# crankSignal.net
KiCad netlist of a schematic drawn in Altium Designer
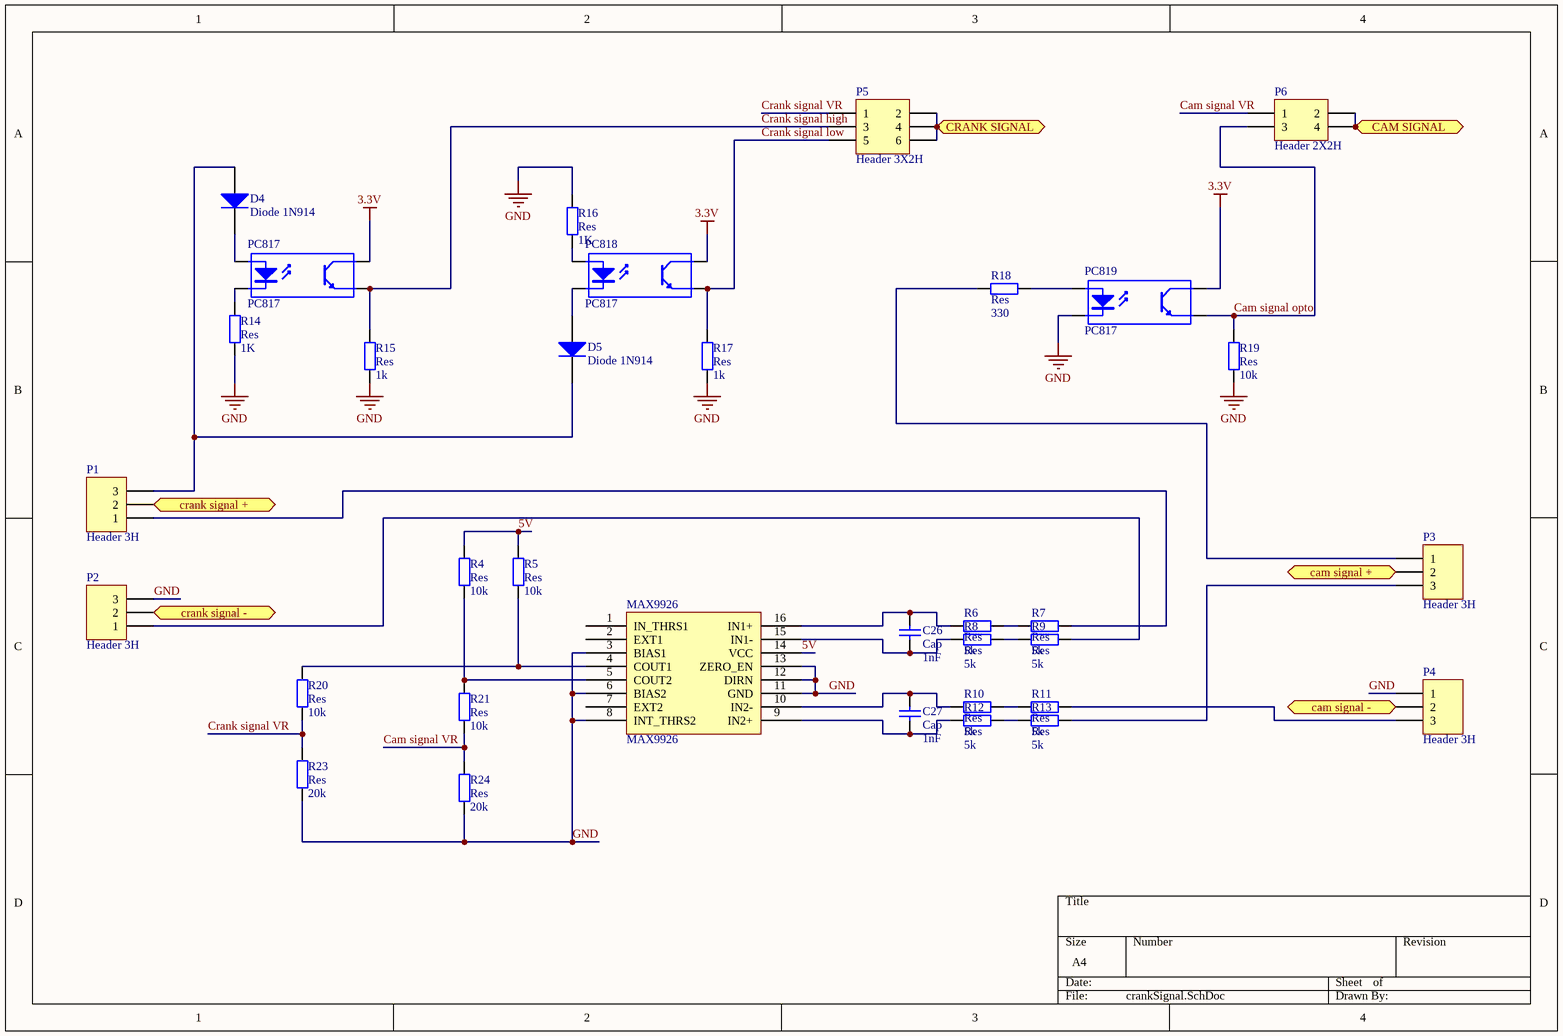
[diagram p0: crankSignal.SchDoc]

(export (version "E")
  (design (tool "Eeschema 10.0.6"))
  (components
    (comp (ref "C26")
      (value "Cap")
      (footprint "1206 footprint")
      (fields (field (name "ALTIUM_VALUE") "1nF"))
      (libsource (lib "ArduinoNano") (part "Cap"))
    )
    (comp (ref "C27")
      (value "Cap")
      (footprint "1206 footprint")
      (fields (field (name "ALTIUM_VALUE") "1nF"))
      (libsource (lib "ArduinoNano") (part "Cap"))
    )
    (comp (ref "D4")
      (value "Diode 1N914")
      (footprint "DO-35")
      (description "High Conductance Fast Diode")
      (fields (field (name "PUBLISHER") "Altium Limited"))
      (libsource (lib "Miscellaneous Devices") (part "Diode 1N914"))
    )
    (comp (ref "D5")
      (value "Diode 1N914")
      (footprint "DO-35")
      (description "High Conductance Fast Diode")
      (fields (field (name "PUBLISHER") "Altium Limited"))
      (libsource (lib "Miscellaneous Devices") (part "Diode 1N914"))
    )
    (comp (ref "MAX9926")
      (value "MAX9926")
      (footprint "MAX9927")
      (libsource (lib "ArduinoNano") (part "MAX9926"))
    )
    (comp (ref "P1")
      (value "Header 3H")
      (footprint "HDR1X3H")
      (description "Header, 3-Pin, Right Angle")
      (fields (field (name "PUBLISHER") "Altium Limited"))
      (libsource (lib "") (part "Header 3H_1"))
    )
    (comp (ref "P2")
      (value "Header 3H")
      (footprint "HDR1X3H")
      (description "Header, 3-Pin, Right Angle")
      (fields (field (name "PUBLISHER") "Altium Limited"))
      (libsource (lib "") (part "Header 3H_1"))
    )
    (comp (ref "P3")
      (value "Header 3H")
      (footprint "HDR1X3H")
      (description "Header, 3-Pin, Right Angle")
      (fields (field (name "PUBLISHER") "Altium Limited"))
      (libsource (lib "Miscellaneous Connectors") (part "Header 3H"))
    )
    (comp (ref "P4")
      (value "Header 3H")
      (footprint "HDR1X3H")
      (description "Header, 3-Pin, Right Angle")
      (fields (field (name "PUBLISHER") "Altium Limited"))
      (libsource (lib "Miscellaneous Connectors") (part "Header 3H"))
    )
    (comp (ref "P5")
      (value "Header 3X2H")
      (footprint "HDR2X3H")
      (description "Header, 3-Pin, Dual row, Right Angle")
      (fields (field (name "PUBLISHER") "Altium Limited"))
      (libsource (lib "Miscellaneous Connectors") (part "Header 3X2H"))
    )
    (comp (ref "P6")
      (value "Header 2X2H")
      (footprint "HDR2X2H")
      (description "Header, 2-Pin, Dual row, Right Angle")
      (fields (field (name "PUBLISHER") "Altium Limited"))
      (libsource (lib "Miscellaneous Connectors") (part "Header 2X2H"))
    )
    (comp (ref "PC817")
      (value "PC817")
      (footprint "PC817 SOP4")
      (libsource (lib "ArduinoNano") (part "PC817"))
    )
    (comp (ref "PC818")
      (value "PC817")
      (footprint "PC817 SOP4")
      (libsource (lib "ArduinoNano") (part "PC817"))
    )
    (comp (ref "PC819")
      (value "PC817")
      (footprint "PC817 SOP4")
      (libsource (lib "ArduinoNano") (part "PC817"))
    )
    (comp (ref "R4")
      (value "Res")
      (footprint "1206 resistor")
      (fields (field (name "ALTIUM_VALUE") "10k"))
      (libsource (lib "") (part "Res_3"))
    )
    (comp (ref "R5")
      (value "Res")
      (footprint "1206 resistor")
      (fields (field (name "ALTIUM_VALUE") "10k"))
      (libsource (lib "") (part "Res_2"))
    )
    (comp (ref "R6")
      (value "Res")
      (footprint "1206 resistor")
      (fields (field (name "ALTIUM_VALUE") "5k"))
      (libsource (lib "ArduinoNano") (part "Res"))
    )
    (comp (ref "R7")
      (value "Res")
      (footprint "1206 resistor")
      (fields (field (name "ALTIUM_VALUE") "5k"))
      (libsource (lib "ArduinoNano") (part "Res"))
    )
    (comp (ref "R8")
      (value "Res")
      (footprint "1206 resistor")
      (fields (field (name "ALTIUM_VALUE") "5k"))
      (libsource (lib "") (part "Res_1"))
    )
    (comp (ref "R9")
      (value "Res")
      (footprint "1206 resistor")
      (fields (field (name "ALTIUM_VALUE") "5k"))
      (libsource (lib "ArduinoNano") (part "Res"))
    )
    (comp (ref "R10")
      (value "Res")
      (footprint "1206 resistor")
      (fields (field (name "ALTIUM_VALUE") "5k"))
      (libsource (lib "ArduinoNano") (part "Res"))
    )
    (comp (ref "R11")
      (value "Res")
      (footprint "1206 resistor")
      (fields (field (name "ALTIUM_VALUE") "5k"))
      (libsource (lib "ArduinoNano") (part "Res"))
    )
    (comp (ref "R12")
      (value "Res")
      (footprint "1206 resistor")
      (fields (field (name "ALTIUM_VALUE") "5k"))
      (libsource (lib "") (part "Res_1"))
    )
    (comp (ref "R13")
      (value "Res")
      (footprint "1206 resistor")
      (fields (field (name "ALTIUM_VALUE") "5k"))
      (libsource (lib "ArduinoNano") (part "Res"))
    )
    (comp (ref "R14")
      (value "Res")
      (footprint "1206 resistor")
      (fields (field (name "ALTIUM_VALUE") "1K"))
      (libsource (lib "") (part "Res_2"))
    )
    (comp (ref "R15")
      (value "Res")
      (footprint "1206 resistor")
      (fields (field (name "ALTIUM_VALUE") "1k"))
      (libsource (lib "") (part "Res_2"))
    )
    (comp (ref "R16")
      (value "Res")
      (footprint "1206 resistor")
      (fields (field (name "ALTIUM_VALUE") "1K"))
      (libsource (lib "") (part "Res_2"))
    )
    (comp (ref "R17")
      (value "Res")
      (footprint "1206 resistor")
      (fields (field (name "ALTIUM_VALUE") "1k"))
      (libsource (lib "") (part "Res_2"))
    )
    (comp (ref "R18")
      (value "Res")
      (footprint "1206 resistor")
      (fields (field (name "ALTIUM_VALUE") "330"))
      (libsource (lib "ArduinoNano") (part "Res"))
    )
    (comp (ref "R19")
      (value "Res")
      (footprint "1206 resistor")
      (fields (field (name "ALTIUM_VALUE") "10k"))
      (libsource (lib "") (part "Res_2"))
    )
    (comp (ref "R20")
      (value "Res")
      (footprint "1206 resistor")
      (fields (field (name "ALTIUM_VALUE") "10k"))
      (libsource (lib "") (part "Res_3"))
    )
    (comp (ref "R21")
      (value "Res")
      (footprint "1206 resistor")
      (fields (field (name "ALTIUM_VALUE") "10k"))
      (libsource (lib "") (part "Res_3"))
    )
    (comp (ref "R23")
      (value "Res")
      (footprint "1206 resistor")
      (fields (field (name "ALTIUM_VALUE") "20k"))
      (libsource (lib "") (part "Res_3"))
    )
    (comp (ref "R24")
      (value "Res")
      (footprint "1206 resistor")
      (fields (field (name "ALTIUM_VALUE") "20k"))
      (libsource (lib "") (part "Res_3"))
    )
  )
  (nets
    (net (code "1") (name "/5V") (class "Default")
      (node (ref "MAX9926") (pin "14") (pinfunction "VCC_14") (pintype "passive"))
      (node (ref "R4") (pin "1") (pinfunction "1_1") (pintype "passive"))
      (node (ref "R5") (pin "2") (pinfunction "2_2") (pintype "passive"))
    )
    (net (code "2") (name "/CAM SIGNAL") (class "Default")
      (node (ref "P6") (pin "2") (pinfunction "2_2") (pintype "passive"))
      (node (ref "P6") (pin "4") (pinfunction "4_4") (pintype "passive"))
    )
    (net (code "3") (name "/CRANK SIGNAL") (class "Default")
      (node (ref "P5") (pin "2") (pinfunction "2_2") (pintype "passive"))
      (node (ref "P5") (pin "4") (pinfunction "4_4") (pintype "passive"))
      (node (ref "P5") (pin "6") (pinfunction "6_6") (pintype "passive"))
    )
    (net (code "4") (name "/Cam signal VR") (class "Default")
      (node (ref "P6") (pin "1") (pinfunction "1_1") (pintype "passive"))
      (node (ref "R21") (pin "2") (pinfunction "2_2") (pintype "passive"))
      (node (ref "R24") (pin "1") (pinfunction "1_1") (pintype "passive"))
    )
    (net (code "5") (name "/Cam signal opto") (class "Default")
      (node (ref "P6") (pin "3") (pinfunction "3_3") (pintype "passive"))
      (node (ref "PC819") (pin "3") (pinfunction "E_3") (pintype "passive"))
      (node (ref "R19") (pin "2") (pinfunction "2_2") (pintype "passive"))
    )
    (net (code "6") (name "/Crank signal VR") (class "Default")
      (node (ref "P5") (pin "1") (pinfunction "1_1") (pintype "passive"))
      (node (ref "R20") (pin "2") (pinfunction "2_2") (pintype "passive"))
      (node (ref "R23") (pin "1") (pinfunction "1_1") (pintype "passive"))
    )
    (net (code "7") (name "/Crank signal high") (class "Default")
      (node (ref "P5") (pin "3") (pinfunction "3_3") (pintype "passive"))
      (node (ref "PC817") (pin "3") (pinfunction "E_3") (pintype "passive"))
      (node (ref "R15") (pin "2") (pinfunction "2_2") (pintype "passive"))
    )
    (net (code "8") (name "/Crank signal low") (class "Default")
      (node (ref "P5") (pin "5") (pinfunction "5_5") (pintype "passive"))
      (node (ref "PC818") (pin "3") (pinfunction "E_3") (pintype "passive"))
      (node (ref "R17") (pin "2") (pinfunction "2_2") (pintype "passive"))
    )
    (net (code "9") (name "/cam signal +") (class "Default")
      (node (ref "P3") (pin "2") (pinfunction "2_2") (pintype "passive"))
    )
    (net (code "10") (name "/cam signal -") (class "Default")
      (node (ref "P4") (pin "2") (pinfunction "2_2") (pintype "passive"))
    )
    (net (code "11") (name "/crank signal +") (class "Default")
      (node (ref "P1") (pin "2") (pinfunction "2_2") (pintype "passive"))
    )
    (net (code "12") (name "/crank signal -") (class "Default")
      (node (ref "P2") (pin "2") (pinfunction "2_2") (pintype "passive"))
    )
    (net (code "13") (name "3.3V") (class "Default")
      (node (ref "PC817") (pin "4") (pinfunction "C_4") (pintype "passive"))
      (node (ref "PC818") (pin "4") (pinfunction "C_4") (pintype "passive"))
      (node (ref "PC819") (pin "4") (pinfunction "C_4") (pintype "passive"))
    )
    (net (code "14") (name "GND") (class "Default")
      (node (ref "MAX9926") (pin "11") (pinfunction "GND_11") (pintype "passive"))
      (node (ref "MAX9926") (pin "12") (pinfunction "DIRN_12") (pintype "passive"))
      (node (ref "MAX9926") (pin "13") (pinfunction "ZERO_EN_13") (pintype "passive"))
      (node (ref "MAX9926") (pin "3") (pinfunction "BIAS1_3") (pintype "passive"))
      (node (ref "MAX9926") (pin "6") (pinfunction "BIAS2_6") (pintype "passive"))
      (node (ref "MAX9926") (pin "8") (pinfunction "INT_THRS2_8") (pintype "passive"))
      (node (ref "P2") (pin "3") (pinfunction "3_3") (pintype "passive"))
      (node (ref "P4") (pin "1") (pinfunction "1_1") (pintype "passive"))
      (node (ref "PC819") (pin "2") (pinfunction "K_2") (pintype "passive"))
      (node (ref "R14") (pin "1") (pinfunction "1_1") (pintype "passive"))
      (node (ref "R15") (pin "1") (pinfunction "1_1") (pintype "passive"))
      (node (ref "R16") (pin "2") (pinfunction "2_2") (pintype "passive"))
      (node (ref "R17") (pin "1") (pinfunction "1_1") (pintype "passive"))
      (node (ref "R19") (pin "1") (pinfunction "1_1") (pintype "passive"))
      (node (ref "R23") (pin "2") (pinfunction "2_2") (pintype "passive"))
      (node (ref "R24") (pin "2") (pinfunction "2_2") (pintype "passive"))
    )
    (net (code "15") (name "Net-(D4-A)") (class "Default")
      (node (ref "D4") (pin "1") (pinfunction "A_1") (pintype "passive"))
      (node (ref "D5") (pin "2") (pinfunction "K_2") (pintype "passive"))
      (node (ref "P1") (pin "3") (pinfunction "3_3") (pintype "passive"))
    )
    (net (code "16") (name "Net-(D4-K)") (class "Default")
      (node (ref "D4") (pin "2") (pinfunction "K_2") (pintype "passive"))
      (node (ref "PC817") (pin "1") (pinfunction "A_1") (pintype "passive"))
    )
    (net (code "17") (name "Net-(D5-A)") (class "Default")
      (node (ref "D5") (pin "1") (pinfunction "A_1") (pintype "passive"))
      (node (ref "PC818") (pin "2") (pinfunction "K_2") (pintype "passive"))
    )
    (net (code "18") (name "Net-(MAX9926-COUT1)") (class "Default")
      (node (ref "MAX9926") (pin "4") (pinfunction "COUT1_4") (pintype "passive"))
      (node (ref "R20") (pin "1") (pinfunction "1_1") (pintype "passive"))
      (node (ref "R5") (pin "1") (pinfunction "1_1") (pintype "passive"))
    )
    (net (code "19") (name "Net-(MAX9926-COUT2)") (class "Default")
      (node (ref "MAX9926") (pin "5") (pinfunction "COUT2_5") (pintype "passive"))
      (node (ref "R21") (pin "1") (pinfunction "1_1") (pintype "passive"))
      (node (ref "R4") (pin "2") (pinfunction "2_2") (pintype "passive"))
    )
    (net (code "20") (name "Net-(MAX9926-IN1+)") (class "Default")
      (node (ref "C26") (pin "2") (pinfunction "2_2") (pintype "passive"))
      (node (ref "MAX9926") (pin "16") (pinfunction "IN1+_16") (pintype "passive"))
      (node (ref "R6") (pin "2") (pinfunction "2_2") (pintype "passive"))
    )
    (net (code "21") (name "Net-(MAX9926-IN1-)") (class "Default")
      (node (ref "C26") (pin "1") (pinfunction "1_1") (pintype "passive"))
      (node (ref "MAX9926") (pin "15") (pinfunction "IN1-_15") (pintype "passive"))
      (node (ref "R8") (pin "1") (pinfunction "1_1") (pintype "passive"))
    )
    (net (code "22") (name "Net-(MAX9926-IN2+)") (class "Default")
      (node (ref "C27") (pin "1") (pinfunction "1_1") (pintype "passive"))
      (node (ref "MAX9926") (pin "9") (pinfunction "IN2+_9") (pintype "passive"))
      (node (ref "R12") (pin "1") (pinfunction "1_1") (pintype "passive"))
    )
    (net (code "23") (name "Net-(MAX9926-IN2-)") (class "Default")
      (node (ref "C27") (pin "2") (pinfunction "2_2") (pintype "passive"))
      (node (ref "MAX9926") (pin "10") (pinfunction "IN2-_10") (pintype "passive"))
      (node (ref "R10") (pin "2") (pinfunction "2_2") (pintype "passive"))
    )
    (net (code "24") (name "Net-(P1-Pad1)") (class "Default")
      (node (ref "P1") (pin "1") (pinfunction "1_1") (pintype "passive"))
      (node (ref "R7") (pin "1") (pinfunction "1_1") (pintype "passive"))
    )
    (net (code "25") (name "Net-(P2-Pad1)") (class "Default")
      (node (ref "P2") (pin "1") (pinfunction "1_1") (pintype "passive"))
      (node (ref "R9") (pin "1") (pinfunction "1_1") (pintype "passive"))
    )
    (net (code "26") (name "Net-(P3-Pad1)") (class "Default")
      (node (ref "P3") (pin "1") (pinfunction "1_1") (pintype "passive"))
      (node (ref "R18") (pin "2") (pinfunction "2_2") (pintype "passive"))
    )
    (net (code "27") (name "Net-(P3-Pad3)") (class "Default")
      (node (ref "P3") (pin "3") (pinfunction "3_3") (pintype "passive"))
      (node (ref "R13") (pin "1") (pinfunction "1_1") (pintype "passive"))
    )
    (net (code "28") (name "Net-(P4-Pad3)") (class "Default")
      (node (ref "P4") (pin "3") (pinfunction "3_3") (pintype "passive"))
      (node (ref "R11") (pin "1") (pinfunction "1_1") (pintype "passive"))
    )
    (net (code "29") (name "Net-(PC817-K)") (class "Default")
      (node (ref "PC817") (pin "2") (pinfunction "K_2") (pintype "passive"))
      (node (ref "R14") (pin "2") (pinfunction "2_2") (pintype "passive"))
    )
    (net (code "30") (name "Net-(PC818-A)") (class "Default")
      (node (ref "PC818") (pin "1") (pinfunction "A_1") (pintype "passive"))
      (node (ref "R16") (pin "1") (pinfunction "1_1") (pintype "passive"))
    )
    (net (code "31") (name "Net-(PC819-A)") (class "Default")
      (node (ref "PC819") (pin "1") (pinfunction "A_1") (pintype "passive"))
      (node (ref "R18") (pin "1") (pinfunction "1_1") (pintype "passive"))
    )
    (net (code "32") (name "Net-(R6-Pad1)") (class "Default")
      (node (ref "R6") (pin "1") (pinfunction "1_1") (pintype "passive"))
      (node (ref "R7") (pin "2") (pinfunction "2_2") (pintype "passive"))
    )
    (net (code "33") (name "Net-(R8-Pad2)") (class "Default")
      (node (ref "R8") (pin "2") (pinfunction "2_2") (pintype "passive"))
      (node (ref "R9") (pin "2") (pinfunction "2_2") (pintype "passive"))
    )
    (net (code "34") (name "Net-(R10-Pad1)") (class "Default")
      (node (ref "R10") (pin "1") (pinfunction "1_1") (pintype "passive"))
      (node (ref "R11") (pin "2") (pinfunction "2_2") (pintype "passive"))
    )
    (net (code "35") (name "Net-(R12-Pad2)") (class "Default")
      (node (ref "R12") (pin "2") (pinfunction "2_2") (pintype "passive"))
      (node (ref "R13") (pin "2") (pinfunction "2_2") (pintype "passive"))
    )
    (net (code "36") (name "unconnected-(MAX9926-EXT1-Pad2)") (class "Default")
      (node (ref "MAX9926") (pin "2") (pinfunction "EXT1_2") (pintype "passive"))
    )
    (net (code "37") (name "unconnected-(MAX9926-EXT2-Pad7)") (class "Default")
      (node (ref "MAX9926") (pin "7") (pinfunction "EXT2_7") (pintype "passive"))
    )
    (net (code "38") (name "unconnected-(MAX9926-IN_THRS1-Pad1)") (class "Default")
      (node (ref "MAX9926") (pin "1") (pinfunction "IN_THRS1_1") (pintype "passive"))
    )
  )
)
